# Breakout_Connections.net
KiCad netlist of a schematic drawn in Altium Designer
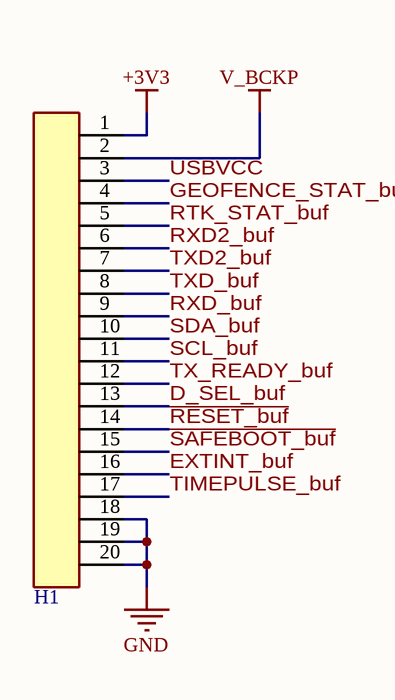
[diagram p0: Breakout Connections.SchDoc]

(export (version "E")
  (design (tool "Eeschema 10.0.6"))
  (components
    (comp (ref "H1")
      (value "1x20 Header")
      (footprint "[Header] 1x20 Male")
      (description "2.54mm pitch")
      (libsource (lib "Connectors") (part "[Header] 1x20 Male"))
    )
  )
  (nets
    (net (code "1") (name "+3V3") (class "Default")
      (node (ref "H1") (pin "1") (pinfunction "1_1") (pintype "passive"))
    )
    (net (code "2") (name "/D_SEL_buf") (class "Default")
      (node (ref "H1") (pin "13") (pinfunction "3_13") (pintype "passive"))
    )
    (net (code "3") (name "/EXTINT_buf") (class "Default")
      (node (ref "H1") (pin "16") (pinfunction "6_16") (pintype "passive"))
    )
    (net (code "4") (name "/GEOFENCE_STAT_buf") (class "Default")
      (node (ref "H1") (pin "4") (pinfunction "4_4") (pintype "passive"))
    )
    (net (code "5") (name "/RESET_buf") (class "Default")
      (node (ref "H1") (pin "14") (pinfunction "4_14") (pintype "passive"))
    )
    (net (code "6") (name "/RTK_STAT_buf") (class "Default")
      (node (ref "H1") (pin "5") (pinfunction "5_5") (pintype "passive"))
    )
    (net (code "7") (name "/RXD2_buf") (class "Default")
      (node (ref "H1") (pin "6") (pinfunction "6_6") (pintype "passive"))
    )
    (net (code "8") (name "/RXD_buf") (class "Default")
      (node (ref "H1") (pin "9") (pinfunction "9_9") (pintype "passive"))
    )
    (net (code "9") (name "/SAFEBOOT_buf") (class "Default")
      (node (ref "H1") (pin "15") (pinfunction "5_15") (pintype "passive"))
    )
    (net (code "10") (name "/SCL_buf") (class "Default")
      (node (ref "H1") (pin "11") (pinfunction "1_11") (pintype "passive"))
    )
    (net (code "11") (name "/SDA_buf") (class "Default")
      (node (ref "H1") (pin "10") (pinfunction "10_10") (pintype "passive"))
    )
    (net (code "12") (name "/TIMEPULSE_buf") (class "Default")
      (node (ref "H1") (pin "17") (pinfunction "7_17") (pintype "passive"))
    )
    (net (code "13") (name "/TXD2_buf") (class "Default")
      (node (ref "H1") (pin "7") (pinfunction "7_7") (pintype "passive"))
    )
    (net (code "14") (name "/TXD_buf") (class "Default")
      (node (ref "H1") (pin "8") (pinfunction "8_8") (pintype "passive"))
    )
    (net (code "15") (name "/TX_READY_buf") (class "Default")
      (node (ref "H1") (pin "12") (pinfunction "2_12") (pintype "passive"))
    )
    (net (code "16") (name "/USBVCC") (class "Default")
      (node (ref "H1") (pin "3") (pinfunction "3_3") (pintype "passive"))
    )
    (net (code "17") (name "GND") (class "Default")
      (node (ref "H1") (pin "18") (pinfunction "8_18") (pintype "passive"))
      (node (ref "H1") (pin "19") (pinfunction "9_19") (pintype "passive"))
      (node (ref "H1") (pin "20") (pinfunction "10_20") (pintype "passive"))
    )
    (net (code "18") (name "V_BCKP") (class "Default")
      (node (ref "H1") (pin "2") (pinfunction "2_2") (pintype "passive"))
    )
  )
)
